# Main.net
KiCad netlist of a schematic drawn in Altium Designer
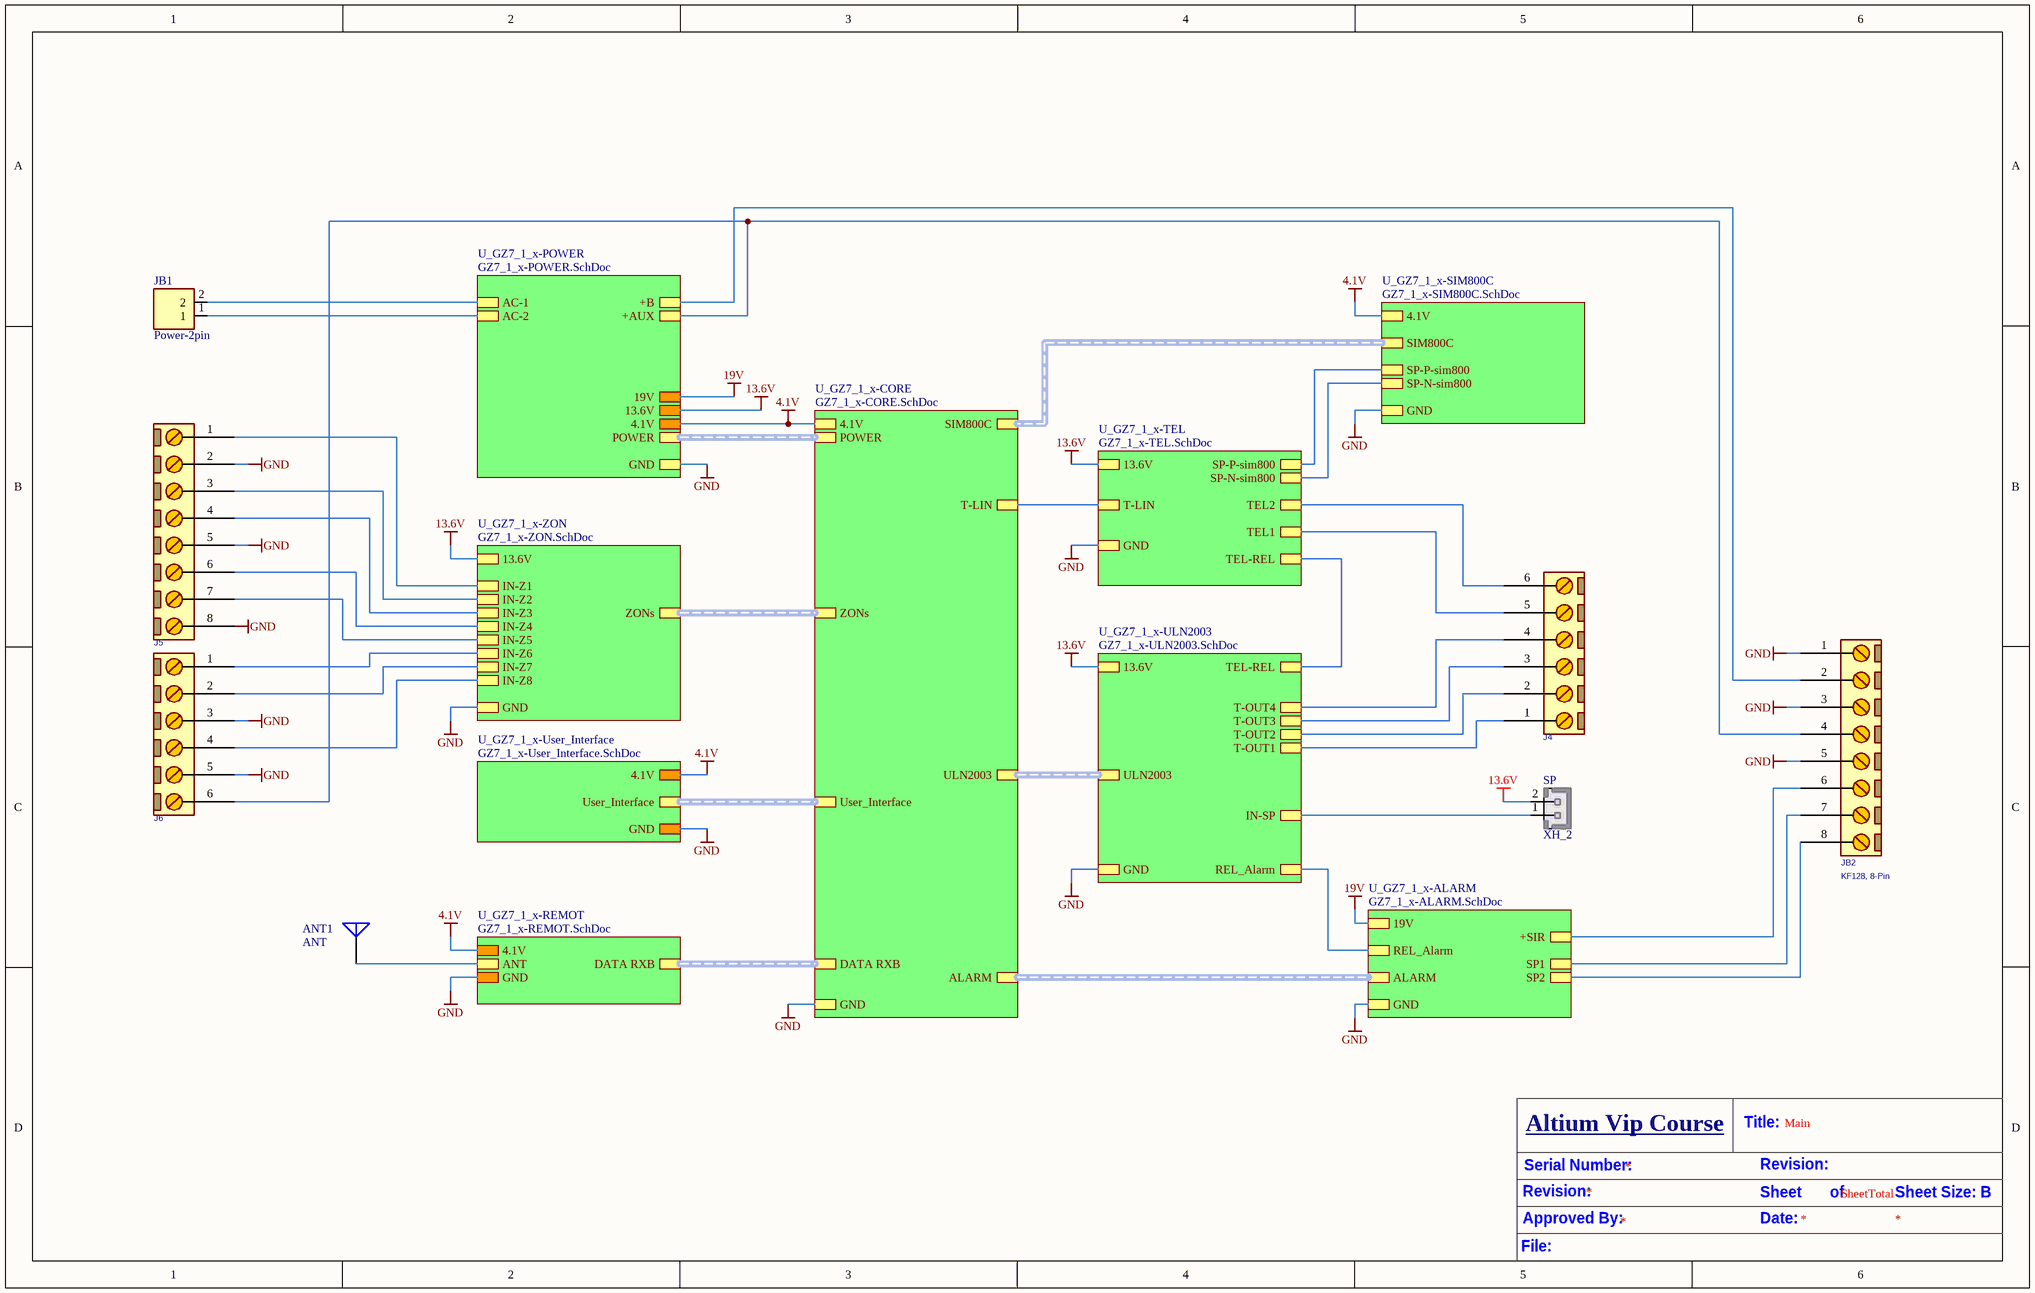
[diagram p0: Main.SchDoc]

(export (version "E")
  (design (tool "Eeschema 10.0.6"))
  (components
    (comp (ref "ANT1")
      (value "ANT")
      (footprint "PAD-ANT")
      (description "Multilayer Chip Antenna")
      (fields (field (name "PUBLISHER") "Altium Limited"))
      (libsource (lib "Miscellaneous Devices") (part "Antenna"))
    )
    (comp (ref "J4")
      (value "CONN_TB6")
      (footprint "T_4_OUT_TEL")
      (description "CONN, TERMINAL BLOCK, 5.08mm pitch")
      (libsource (lib "") (part "CONN_TB6_1"))
    )
    (comp (ref "J5")
      (value "CONN_TB8")
      (footprint "CON-Z_1_4")
      (description "CONN, TERMINAL BLOCK, 5.08mm pitch")
      (libsource (lib "conn_terminalB") (part "CONN_TB8"))
    )
    (comp (ref "J6")
      (value "CONN_TB6")
      (footprint "CON-Z_5_8")
      (description "CONN, TERMINAL BLOCK, 5.08mm pitch")
      (libsource (lib "conn_terminalB") (part "CONN_TB6"))
    )
    (comp (ref "JB1")
      (value "Power-2pin")
      (footprint "PWL_2")
      (description "Power Terminal 2pin,Header, 2-Pin")
      (libsource (lib "conn_power") (part "CONN_PWL_2"))
    )
    (comp (ref "JB2")
      (value "KF128, 8-Pin")
      (footprint "CON8-AUX")
      (description "CONN, TERMINAL BLOCK, 5.08mm pitch")
      (libsource (lib "") (part "CONN_TB8_1"))
    )
    (comp (ref "SP")
      (value "XH_2")
      (footprint "XH_2")
      (description "PW10-x-M, JST-BxB-XH-A pitch: 2.5mm, 3A/250v")
      (fields (field (name "MANF") "JST") (field (name "MANF_P#") "B2B-XH-A"))
      (libsource (lib "conn_wire2board") (part "XH_2"))
    )
  )
  (nets
    (net (code "1") (name "/+AUX") (class "Default")
      (node (ref "J6") (pin "6") (pinfunction "6_6") (pintype "passive"))
      (node (ref "JB2") (pin "4") (pinfunction "4_4") (pintype "passive"))
    )
    (net (code "2") (name "/+B") (class "Default")
      (node (ref "JB2") (pin "2") (pinfunction "2_2") (pintype "passive"))
    )
    (net (code "3") (name "/+SIR") (class "Default")
      (node (ref "JB2") (pin "6") (pinfunction "6_6") (pintype "passive"))
    )
    (net (code "4") (name "/AC-1") (class "Default")
      (node (ref "JB1") (pin "2") (pinfunction "2_2") (pintype "passive"))
    )
    (net (code "5") (name "/AC-2") (class "Default")
      (node (ref "JB1") (pin "1") (pinfunction "1_1") (pintype "passive"))
    )
    (net (code "7") (name "/ANT") (class "Default")
      (node (ref "ANT1") (pin "1") (pinfunction "A_1") (pintype "passive"))
    )
    (net (code "9") (name "/IN-SP") (class "Default")
      (node (ref "SP") (pin "1") (pinfunction "1_1") (pintype "passive"))
    )
    (net (code "10") (name "/IN-Z1") (class "Default")
      (node (ref "J5") (pin "1") (pinfunction "1_1") (pintype "passive"))
    )
    (net (code "11") (name "/IN-Z2") (class "Default")
      (node (ref "J5") (pin "3") (pinfunction "3_3") (pintype "passive"))
    )
    (net (code "12") (name "/IN-Z3") (class "Default")
      (node (ref "J5") (pin "4") (pinfunction "4_4") (pintype "passive"))
    )
    (net (code "13") (name "/IN-Z4") (class "Default")
      (node (ref "J5") (pin "6") (pinfunction "6_6") (pintype "passive"))
    )
    (net (code "14") (name "/IN-Z5") (class "Default")
      (node (ref "J5") (pin "7") (pinfunction "7_7") (pintype "passive"))
    )
    (net (code "15") (name "/IN-Z6") (class "Default")
      (node (ref "J6") (pin "1") (pinfunction "1_1") (pintype "passive"))
    )
    (net (code "16") (name "/IN-Z7") (class "Default")
      (node (ref "J6") (pin "2") (pinfunction "2_2") (pintype "passive"))
    )
    (net (code "17") (name "/IN-Z8") (class "Default")
      (node (ref "J6") (pin "4") (pinfunction "4_4") (pintype "passive"))
    )
    (net (code "23") (name "/SP1") (class "Default")
      (node (ref "JB2") (pin "7") (pinfunction "7_7") (pintype "passive"))
    )
    (net (code "24") (name "/SP2") (class "Default")
      (node (ref "JB2") (pin "8") (pinfunction "8_8") (pintype "passive"))
    )
    (net (code "26") (name "/T-OUT1") (class "Default")
      (node (ref "J4") (pin "1") (pinfunction "1_1") (pintype "passive"))
    )
    (net (code "27") (name "/T-OUT2") (class "Default")
      (node (ref "J4") (pin "2") (pinfunction "2_2") (pintype "passive"))
    )
    (net (code "28") (name "/T-OUT3") (class "Default")
      (node (ref "J4") (pin "3") (pinfunction "3_3") (pintype "passive"))
    )
    (net (code "29") (name "/T-OUT4") (class "Default")
      (node (ref "J4") (pin "4") (pinfunction "4_4") (pintype "passive"))
    )
    (net (code "31") (name "/TEL1") (class "Default")
      (node (ref "J4") (pin "5") (pinfunction "5_5") (pintype "passive"))
    )
    (net (code "32") (name "/TEL2") (class "Default")
      (node (ref "J4") (pin "6") (pinfunction "6_6") (pintype "passive"))
    )
    (net (code "37") (name "13.6V") (class "Default")
      (node (ref "SP") (pin "2") (pinfunction "2_2") (pintype "passive"))
    )
    (net (code "39") (name "GND") (class "Default")
      (node (ref "J5") (pin "2") (pinfunction "2_2") (pintype "passive"))
      (node (ref "J5") (pin "5") (pinfunction "5_5") (pintype "passive"))
      (node (ref "J5") (pin "8") (pinfunction "8_8") (pintype "passive"))
      (node (ref "J6") (pin "3") (pinfunction "3_3") (pintype "passive"))
      (node (ref "J6") (pin "5") (pinfunction "5_5") (pintype "passive"))
      (node (ref "JB2") (pin "1") (pinfunction "1_1") (pintype "passive"))
      (node (ref "JB2") (pin "3") (pinfunction "3_3") (pintype "passive"))
      (node (ref "JB2") (pin "5") (pinfunction "5_5") (pintype "passive"))
    )
  )
)
